# ARM_TOOLING.net
KiCad netlist of a schematic drawn in Altium Designer
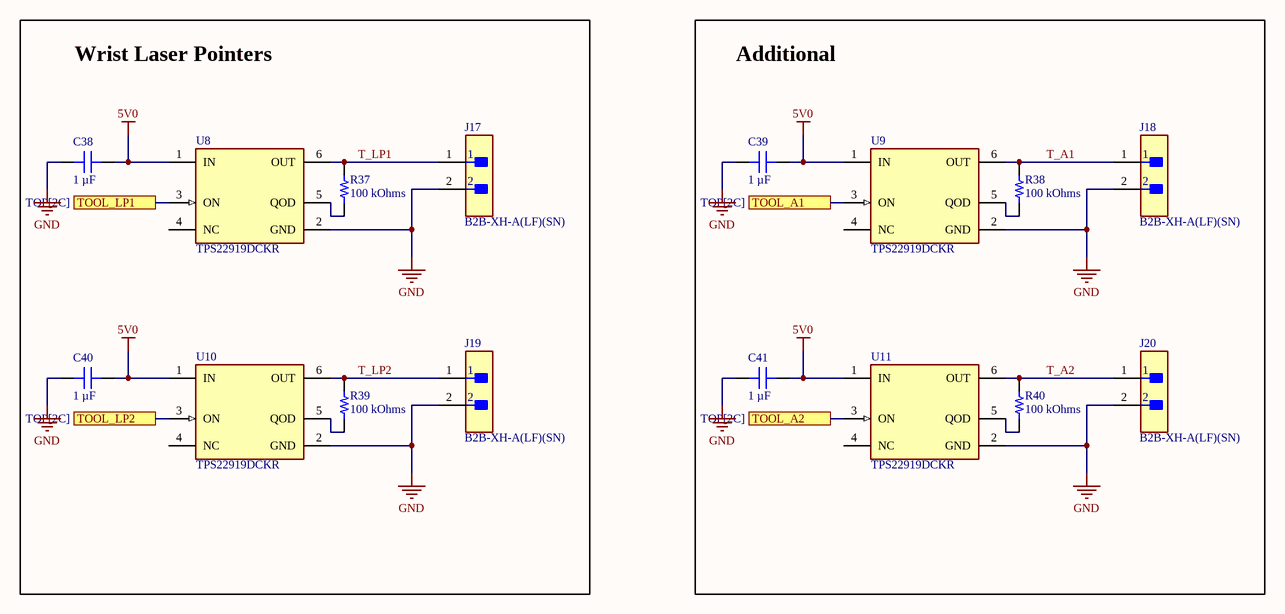
[diagram p0: ARM_TOOLING.SchDoc]

(export (version "E")
  (design (tool "Eeschema 10.0.6"))
  (components
    (comp (ref "C38")
      (value "1 µF")
      (footprint "CAP 0603_1608")
      (description "CAP0603 X7R 1UF 10% 50V")
      (fields
        (field (name "PART NUMBER") "GMC10X7R105K50NT")
        (field (name "MANUFACTURER") "Cal-Chip Electronics, Inc.")
      )
      (libsource (lib "Celestial Altium Library - altium_library") (part "Capacitor"))
    )
    (comp (ref "C39")
      (value "1 µF")
      (footprint "CAP 0603_1608")
      (description "CAP0603 X7R 1UF 10% 50V")
      (fields
        (field (name "PART NUMBER") "GMC10X7R105K50NT")
        (field (name "MANUFACTURER") "Cal-Chip Electronics, Inc.")
      )
      (libsource (lib "Celestial Altium Library - altium_library") (part "Capacitor"))
    )
    (comp (ref "C40")
      (value "1 µF")
      (footprint "CAP 0603_1608")
      (description "CAP0603 X7R 1UF 10% 50V")
      (fields
        (field (name "PART NUMBER") "GMC10X7R105K50NT")
        (field (name "MANUFACTURER") "Cal-Chip Electronics, Inc.")
      )
      (libsource (lib "Celestial Altium Library - altium_library") (part "Capacitor"))
    )
    (comp (ref "C41")
      (value "1 µF")
      (footprint "CAP 0603_1608")
      (description "CAP0603 X7R 1UF 10% 50V")
      (fields
        (field (name "PART NUMBER") "GMC10X7R105K50NT")
        (field (name "MANUFACTURER") "Cal-Chip Electronics, Inc.")
      )
      (libsource (lib "Celestial Altium Library - altium_library") (part "Capacitor"))
    )
    (comp (ref "J17")
      (value "B2B-XH-A(LF)(SN)")
      (footprint "FP-B2B-XH-A_LF_SN-MFG")
      (description "CONN HEADER VERT 2POS 2.5MM")
      (libsource (lib "Altium Content Vault") (part "3bc925449376181038e59eaffc5286c"))
    )
    (comp (ref "J18")
      (value "B2B-XH-A(LF)(SN)")
      (footprint "FP-B2B-XH-A_LF_SN-MFG")
      (description "CONN HEADER VERT 2POS 2.5MM")
      (libsource (lib "Altium Content Vault") (part "3bc925449376181038e59eaffc5286c"))
    )
    (comp (ref "J19")
      (value "B2B-XH-A(LF)(SN)")
      (footprint "FP-B2B-XH-A_LF_SN-MFG")
      (description "CONN HEADER VERT 2POS 2.5MM")
      (libsource (lib "Altium Content Vault") (part "3bc925449376181038e59eaffc5286c"))
    )
    (comp (ref "J20")
      (value "B2B-XH-A(LF)(SN)")
      (footprint "FP-B2B-XH-A_LF_SN-MFG")
      (description "CONN HEADER VERT 2POS 2.5MM")
      (libsource (lib "Altium Content Vault") (part "3bc925449376181038e59eaffc5286c"))
    )
    (comp (ref "R37")
      (value "100 kOhms")
      (footprint "RES 0603_1608")
      (description "RES 100 KOHMS 0.1% 0.15W 0603")
      (fields
        (field (name "PART NUMBER") "RQ73C1J100KBTD")
        (field (name "MANUFACTURER") "TE Connectivity Passive Product")
      )
      (libsource (lib "Celestial Altium Library - altium_library") (part "Resistor"))
    )
    (comp (ref "R38")
      (value "100 kOhms")
      (footprint "RES 0603_1608")
      (description "RES 100 KOHMS 0.1% 0.15W 0603")
      (fields
        (field (name "PART NUMBER") "RQ73C1J100KBTD")
        (field (name "MANUFACTURER") "TE Connectivity Passive Product")
      )
      (libsource (lib "Celestial Altium Library - altium_library") (part "Resistor"))
    )
    (comp (ref "R39")
      (value "100 kOhms")
      (footprint "RES 0603_1608")
      (description "RES 100 KOHMS 0.1% 0.15W 0603")
      (fields
        (field (name "PART NUMBER") "RQ73C1J100KBTD")
        (field (name "MANUFACTURER") "TE Connectivity Passive Product")
      )
      (libsource (lib "Celestial Altium Library - altium_library") (part "Resistor"))
    )
    (comp (ref "R40")
      (value "100 kOhms")
      (footprint "RES 0603_1608")
      (description "RES 100 KOHMS 0.1% 0.15W 0603")
      (fields
        (field (name "PART NUMBER") "RQ73C1J100KBTD")
        (field (name "MANUFACTURER") "TE Connectivity Passive Product")
      )
      (libsource (lib "Celestial Altium Library - altium_library") (part "Resistor"))
    )
    (comp (ref "U8")
      (value "TPS22919DCKR")
      (footprint "FP-DCK0006A-MFG")
      (description "POWER MANAGEMENT")
      (libsource (lib "Altium Content Vault") (part "7dede5ae6ec4f64f362f8612ed9bb45"))
    )
    (comp (ref "U9")
      (value "TPS22919DCKR")
      (footprint "FP-DCK0006A-MFG")
      (description "POWER MANAGEMENT")
      (libsource (lib "Altium Content Vault") (part "7dede5ae6ec4f64f362f8612ed9bb45"))
    )
    (comp (ref "U10")
      (value "TPS22919DCKR")
      (footprint "FP-DCK0006A-MFG")
      (description "POWER MANAGEMENT")
      (libsource (lib "Altium Content Vault") (part "7dede5ae6ec4f64f362f8612ed9bb45"))
    )
    (comp (ref "U11")
      (value "TPS22919DCKR")
      (footprint "FP-DCK0006A-MFG")
      (description "POWER MANAGEMENT")
      (libsource (lib "Altium Content Vault") (part "7dede5ae6ec4f64f362f8612ed9bb45"))
    )
  )
  (nets
    (net (code "1") (name "/TOOL_A1") (class "Default")
      (node (ref "U9") (pin "3") (pinfunction "ON_3") (pintype "input"))
    )
    (net (code "2") (name "/TOOL_A2") (class "Default")
      (node (ref "U11") (pin "3") (pinfunction "ON_3") (pintype "input"))
    )
    (net (code "3") (name "/TOOL_LP1") (class "Default")
      (node (ref "U8") (pin "3") (pinfunction "ON_3") (pintype "input"))
    )
    (net (code "4") (name "/TOOL_LP2") (class "Default")
      (node (ref "U10") (pin "3") (pinfunction "ON_3") (pintype "input"))
    )
    (net (code "5") (name "/T_A1") (class "Default")
      (node (ref "J18") (pin "1") (pinfunction "1_1") (pintype "passive"))
      (node (ref "R38") (pin "2") (pinfunction "2_2") (pintype "passive"))
      (node (ref "U9") (pin "6") (pinfunction "OUT_6") (pintype "power_in"))
    )
    (net (code "6") (name "/T_A2") (class "Default")
      (node (ref "J20") (pin "1") (pinfunction "1_1") (pintype "passive"))
      (node (ref "R40") (pin "2") (pinfunction "2_2") (pintype "passive"))
      (node (ref "U11") (pin "6") (pinfunction "OUT_6") (pintype "power_in"))
    )
    (net (code "7") (name "/T_LP1") (class "Default")
      (node (ref "J17") (pin "1") (pinfunction "1_1") (pintype "passive"))
      (node (ref "R37") (pin "2") (pinfunction "2_2") (pintype "passive"))
      (node (ref "U8") (pin "6") (pinfunction "OUT_6") (pintype "power_in"))
    )
    (net (code "8") (name "/T_LP2") (class "Default")
      (node (ref "J19") (pin "1") (pinfunction "1_1") (pintype "passive"))
      (node (ref "R39") (pin "2") (pinfunction "2_2") (pintype "passive"))
      (node (ref "U10") (pin "6") (pinfunction "OUT_6") (pintype "power_in"))
    )
    (net (code "9") (name "5V0") (class "Default")
      (node (ref "C38") (pin "2") (pinfunction "2_2") (pintype "passive"))
      (node (ref "C39") (pin "2") (pinfunction "2_2") (pintype "passive"))
      (node (ref "C40") (pin "2") (pinfunction "2_2") (pintype "passive"))
      (node (ref "C41") (pin "2") (pinfunction "2_2") (pintype "passive"))
      (node (ref "U10") (pin "1") (pinfunction "IN_1") (pintype "power_in"))
      (node (ref "U11") (pin "1") (pinfunction "IN_1") (pintype "power_in"))
      (node (ref "U8") (pin "1") (pinfunction "IN_1") (pintype "power_in"))
      (node (ref "U9") (pin "1") (pinfunction "IN_1") (pintype "power_in"))
    )
    (net (code "10") (name "GND") (class "Default")
      (node (ref "C38") (pin "1") (pinfunction "1_1") (pintype "passive"))
      (node (ref "C39") (pin "1") (pinfunction "1_1") (pintype "passive"))
      (node (ref "C40") (pin "1") (pinfunction "1_1") (pintype "passive"))
      (node (ref "C41") (pin "1") (pinfunction "1_1") (pintype "passive"))
      (node (ref "J17") (pin "2") (pinfunction "2_2") (pintype "passive"))
      (node (ref "J18") (pin "2") (pinfunction "2_2") (pintype "passive"))
      (node (ref "J19") (pin "2") (pinfunction "2_2") (pintype "passive"))
      (node (ref "J20") (pin "2") (pinfunction "2_2") (pintype "passive"))
      (node (ref "U10") (pin "2") (pinfunction "GND_2") (pintype "power_in"))
      (node (ref "U11") (pin "2") (pinfunction "GND_2") (pintype "power_in"))
      (node (ref "U8") (pin "2") (pinfunction "GND_2") (pintype "power_in"))
      (node (ref "U9") (pin "2") (pinfunction "GND_2") (pintype "power_in"))
    )
    (net (code "11") (name "Net-(U8-QOD)") (class "Default")
      (node (ref "R37") (pin "1") (pinfunction "1_1") (pintype "passive"))
      (node (ref "U8") (pin "5") (pinfunction "QOD_5") (pintype "passive"))
    )
    (net (code "12") (name "Net-(U9-QOD)") (class "Default")
      (node (ref "R38") (pin "1") (pinfunction "1_1") (pintype "passive"))
      (node (ref "U9") (pin "5") (pinfunction "QOD_5") (pintype "passive"))
    )
    (net (code "13") (name "Net-(U10-QOD)") (class "Default")
      (node (ref "R39") (pin "1") (pinfunction "1_1") (pintype "passive"))
      (node (ref "U10") (pin "5") (pinfunction "QOD_5") (pintype "passive"))
    )
    (net (code "14") (name "Net-(U11-QOD)") (class "Default")
      (node (ref "R40") (pin "1") (pinfunction "1_1") (pintype "passive"))
      (node (ref "U11") (pin "5") (pinfunction "QOD_5") (pintype "passive"))
    )
    (net (code "15") (name "unconnected-(U8-NC-Pad4)") (class "Default")
      (node (ref "U8") (pin "4") (pinfunction "NC_4") (pintype "passive"))
    )
    (net (code "16") (name "unconnected-(U9-NC-Pad4)") (class "Default")
      (node (ref "U9") (pin "4") (pinfunction "NC_4") (pintype "passive"))
    )
    (net (code "17") (name "unconnected-(U10-NC-Pad4)") (class "Default")
      (node (ref "U10") (pin "4") (pinfunction "NC_4") (pintype "passive"))
    )
    (net (code "18") (name "unconnected-(U11-NC-Pad4)") (class "Default")
      (node (ref "U11") (pin "4") (pinfunction "NC_4") (pintype "passive"))
    )
  )
)
